# CarloopStick-v1_1.net
KiCad netlist of a schematic drawn in EAGLE
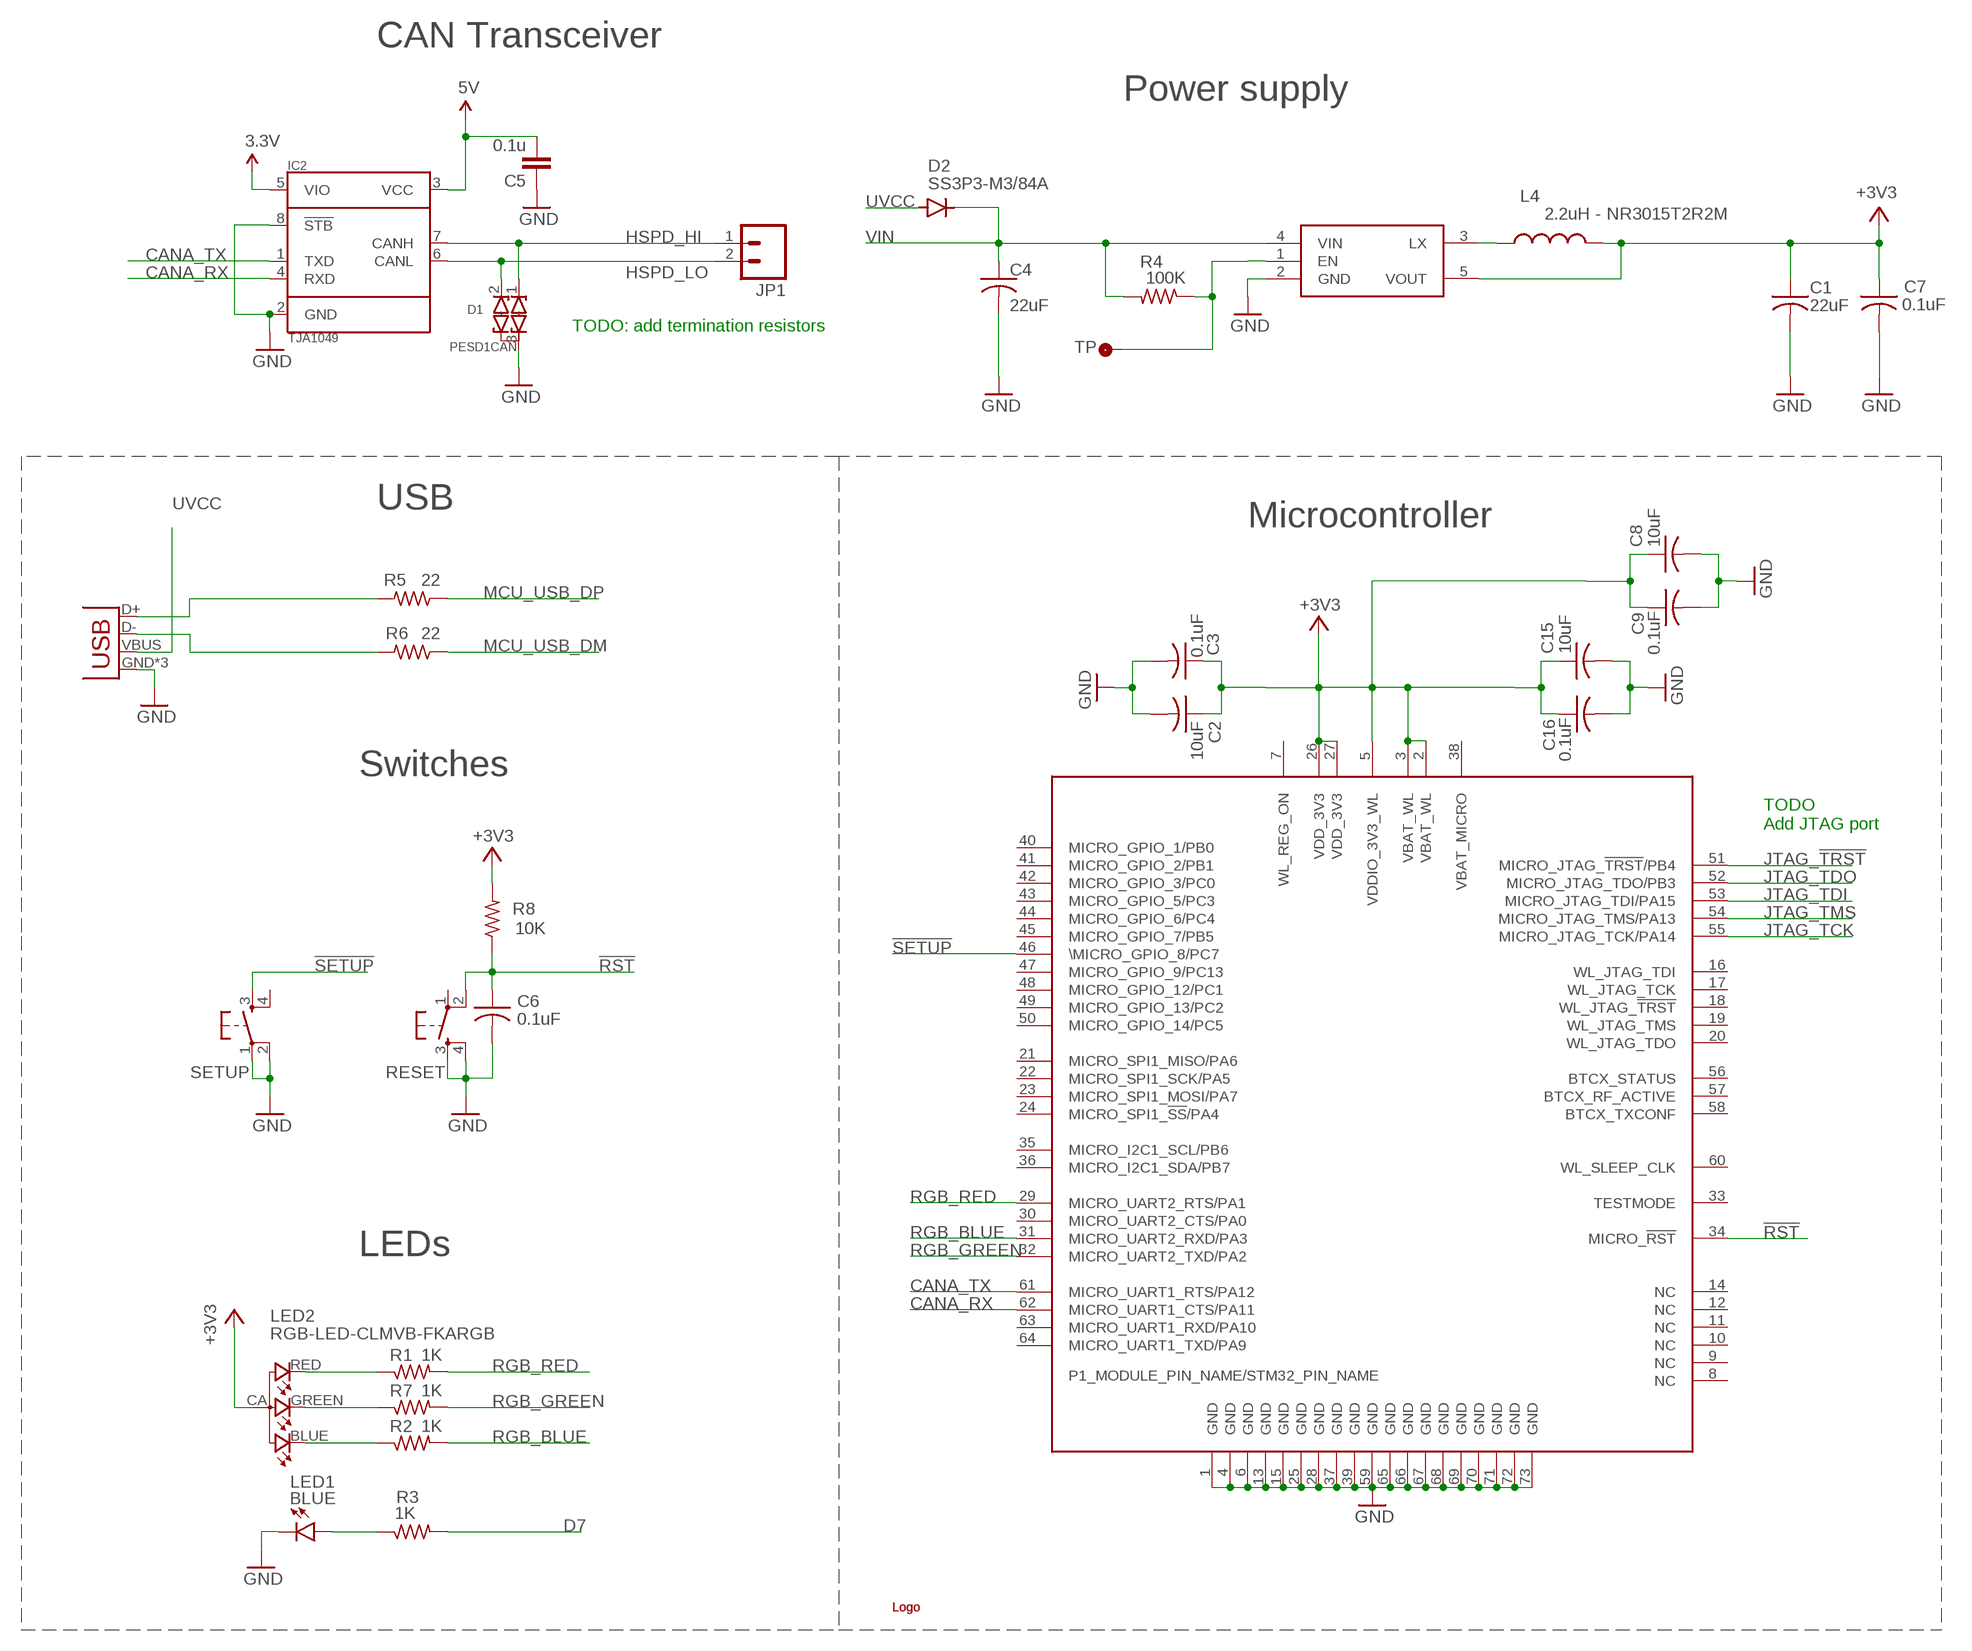
[diagram p0: schematic, sheet 1]

(export (version "E")
  (design (tool "Eeschema 10.0.6"))
  (components
    (comp (ref "C1")
      (value "22uF")
      (footprint "eagle-import:C0603_B")
      (libsource (lib "eagle-import") (part "C-US0603"))
    )
    (comp (ref "C2")
      (value "10uF")
      (footprint "eagle-import:C0603_B")
      (libsource (lib "eagle-import") (part "C-US0603"))
    )
    (comp (ref "C3")
      (value "0.1uF")
      (footprint "eagle-import:C0402_B")
      (libsource (lib "eagle-import") (part "C-US"))
    )
    (comp (ref "C4")
      (value "22uF")
      (footprint "eagle-import:C0603_B")
      (libsource (lib "eagle-import") (part "C-US0603"))
    )
    (comp (ref "C5")
      (value "0.1u")
      (footprint "eagle-import:C0402")
      (fields (field (name "PARTNO") "GRM155R71C104KA88D"))
      (libsource (lib "eagle-import") (part "C-EUC0402"))
    )
    (comp (ref "C6")
      (value "0.1uF")
      (footprint "eagle-import:C0402_B")
      (libsource (lib "eagle-import") (part "C-US"))
    )
    (comp (ref "C7")
      (value "0.1uF")
      (footprint "eagle-import:C0402_B")
      (libsource (lib "eagle-import") (part "C-US"))
    )
    (comp (ref "C8")
      (value "10uF")
      (footprint "eagle-import:C0603_B")
      (libsource (lib "eagle-import") (part "C-US0603"))
    )
    (comp (ref "C9")
      (value "0.1uF")
      (footprint "eagle-import:C0402_B")
      (libsource (lib "eagle-import") (part "C-US"))
    )
    (comp (ref "C15")
      (value "10uF")
      (footprint "eagle-import:C0603_B")
      (libsource (lib "eagle-import") (part "C-US0603"))
    )
    (comp (ref "C16")
      (value "0.1uF")
      (footprint "eagle-import:C0402_B")
      (libsource (lib "eagle-import") (part "C-US"))
    )
    (comp (ref "D1")
      (value "PESD1CAN")
      (footprint "eagle-import:SOT23")
      (fields (field (name "PARTNO") "PESD1CAN-215"))
      (libsource (lib "eagle-import") (part "DIODE_ESD_DUAL-SOT-23"))
    )
    (comp (ref "D2")
      (value "SS3P3-M3/84A")
      (footprint "eagle-import:DIODE-DO-220AA(SMP)")
      (libsource (lib "eagle-import") (part "DIODE"))
    )
    (comp (ref "IC2")
      (value "TJA1049")
      (footprint "eagle-import:SO8")
      (fields (field (name "PARTNO") "TJA1049T-118"))
      (libsource (lib "eagle-import") (part "TJA1049"))
    )
    (comp (ref "JP1")
      (value "M02PTH")
      (footprint "eagle-import:1X02")
      (libsource (lib "eagle-import") (part "M02PTH"))
    )
    (comp (ref "L4")
      (value "2.2uH - NR3015T2R2M")
      (footprint "eagle-import:INDUCTOR-NR3015")
      (libsource (lib "eagle-import") (part "INDUCTORB"))
    )
    (comp (ref "LED2")
      (value "RGB-LED-CLMVB-FKARGB")
      (footprint "eagle-import:PLCC4-2MM-RGB")
      (libsource (lib "eagle-import") (part "RGB-LED-CLMVB-FKARGB"))
    )
    (comp (ref "LED_USR")
      (value "BLUE")
      (footprint "eagle-import:LED-0603-NO-SS")
      (libsource (lib "eagle-import") (part "LED-0603-NO-SS"))
    )
    (comp (ref "R1")
      (value "1K")
      (footprint "eagle-import:R0402_B")
      (libsource (lib "eagle-import") (part "R-US_"))
    )
    (comp (ref "R2")
      (value "1K")
      (footprint "eagle-import:R0402_B")
      (libsource (lib "eagle-import") (part "R-US_"))
    )
    (comp (ref "R3")
      (value "1K")
      (footprint "eagle-import:R0402_B")
      (libsource (lib "eagle-import") (part "R-US_"))
    )
    (comp (ref "R4")
      (value "100K")
      (footprint "eagle-import:R0402_B")
      (libsource (lib "eagle-import") (part "R-US_"))
    )
    (comp (ref "R5")
      (value "22")
      (footprint "eagle-import:R0402_B")
      (libsource (lib "eagle-import") (part "R-US_"))
    )
    (comp (ref "R6")
      (value "22")
      (footprint "eagle-import:R0402_B")
      (libsource (lib "eagle-import") (part "R-US_"))
    )
    (comp (ref "R7")
      (value "1K")
      (footprint "eagle-import:R0402_B")
      (libsource (lib "eagle-import") (part "R-US_"))
    )
    (comp (ref "R8")
      (value "10K")
      (footprint "eagle-import:R0402_B")
      (libsource (lib "eagle-import") (part "R-US_"))
    )
    (comp (ref "RESET")
      (value "KMR211GLFS")
      (footprint "eagle-import:TACTILE_SWITCH_SMD")
      (libsource (lib "eagle-import") (part "TAC_SWITCHSMD"))
    )
    (comp (ref "SETUP")
      (value "KMR211GLFS")
      (footprint "eagle-import:TACTILE_SWITCH_SMD")
      (libsource (lib "eagle-import") (part "TAC_SWITCHSMD"))
    )
    (comp (ref "U$1")
      (value "LOGOSMALL")
      (footprint "eagle-import:CARLOOP-2")
      (libsource (lib "eagle-import") (part "LOGOSMALL"))
    )
    (comp (ref "U$4")
      (value "P1")
      (footprint "eagle-import:WM-N-BM-14")
      (libsource (lib "eagle-import") (part "P1"))
    )
    (comp (ref "U$5")
      (value "LOGOSMALL")
      (footprint "eagle-import:CARLOOP-2")
      (libsource (lib "eagle-import") (part "LOGOSMALL"))
    )
    (comp (ref "U$11")
      (value "R8008-33")
      (footprint "eagle-import:SOT23-5")
      (libsource (lib "eagle-import") (part "R8008-33"))
    )
    (comp (ref "U$12")
      (value "TP3")
      (footprint "eagle-import:TP60_BOT")
      (libsource (lib "eagle-import") (part "TP3"))
    )
    (comp (ref "X1")
      (value "USB-MICROB")
      (footprint "eagle-import:USB-MICROB-SLOT-HOLE")
      (libsource (lib "eagle-import") (part "USBUSB-MICROB-SLOT-HOLE"))
    )
  )
  (nets
    (net (code "1") (name "+3V3") (class "Default")
      (node (ref "C1") (pin "1") (pinfunction "1_1") (pintype "passive"))
      (node (ref "C15") (pin "1") (pinfunction "1_1") (pintype "passive"))
      (node (ref "C16") (pin "1") (pinfunction "1_1") (pintype "passive"))
      (node (ref "C2") (pin "1") (pinfunction "1_1") (pintype "passive"))
      (node (ref "C3") (pin "1") (pinfunction "1_1") (pintype "passive"))
      (node (ref "C7") (pin "1") (pinfunction "1_1") (pintype "passive"))
      (node (ref "C8") (pin "1") (pinfunction "1_1") (pintype "passive"))
      (node (ref "C9") (pin "1") (pinfunction "1_1") (pintype "passive"))
      (node (ref "L4") (pin "2") (pinfunction "2_2") (pintype "passive"))
      (node (ref "LED2") (pin "CA") (pinfunction "1_CA") (pintype "passive"))
      (node (ref "R8") (pin "2") (pinfunction "2_2") (pintype "passive"))
      (node (ref "U$11") (pin "5") (pinfunction "VOUT_5") (pintype "bidirectional"))
      (node (ref "U$4") (pin "2") (pinfunction "VBAT_WL_2") (pintype "bidirectional"))
      (node (ref "U$4") (pin "26") (pinfunction "VDD_3V3_26") (pintype "bidirectional"))
      (node (ref "U$4") (pin "27") (pinfunction "VDD_3V3_27") (pintype "bidirectional"))
      (node (ref "U$4") (pin "3") (pinfunction "VBAT_WL_3") (pintype "bidirectional"))
      (node (ref "U$4") (pin "5") (pinfunction "VDDIO_3V3_WL_5") (pintype "bidirectional"))
    )
    (net (code "2") (name "/CANA_RX") (class "Default")
      (node (ref "IC2") (pin "4") (pinfunction "RXD_4") (pintype "bidirectional"))
      (node (ref "U$4") (pin "62") (pinfunction "MICRO_UART1_CTS/PA11_62") (pintype "bidirectional"))
    )
    (net (code "3") (name "/CANA_TX") (class "Default")
      (node (ref "IC2") (pin "1") (pinfunction "TXD_1") (pintype "bidirectional"))
      (node (ref "U$4") (pin "61") (pinfunction "MICRO_UART1_RTS/PA12_61") (pintype "bidirectional"))
    )
    (net (code "4") (name "/D7") (class "Default")
      (node (ref "R3") (pin "2") (pinfunction "2_2") (pintype "passive"))
    )
    (net (code "5") (name "/HSPD_HI") (class "Default")
      (node (ref "D1") (pin "1") (pinfunction "C1_1") (pintype "power_in"))
      (node (ref "IC2") (pin "7") (pinfunction "CANH_7") (pintype "bidirectional"))
      (node (ref "JP1") (pin "1") (pinfunction "1_1") (pintype "passive"))
    )
    (net (code "6") (name "/HSPD_LO") (class "Default")
      (node (ref "D1") (pin "2") (pinfunction "C2_2") (pintype "power_in"))
      (node (ref "IC2") (pin "6") (pinfunction "CANL_6") (pintype "bidirectional"))
      (node (ref "JP1") (pin "2") (pinfunction "2_2") (pintype "passive"))
    )
    (net (code "7") (name "/JTAG_TCK") (class "Default")
      (node (ref "U$4") (pin "55") (pinfunction "MICRO_JTAG_TCK/PA14_55") (pintype "bidirectional"))
    )
    (net (code "8") (name "/JTAG_TDI") (class "Default")
      (node (ref "U$4") (pin "53") (pinfunction "MICRO_JTAG_TDI/PA15_53") (pintype "bidirectional"))
    )
    (net (code "9") (name "/JTAG_TDO") (class "Default")
      (node (ref "U$4") (pin "52") (pinfunction "MICRO_JTAG_TDO/PB3_52") (pintype "bidirectional"))
    )
    (net (code "10") (name "/JTAG_TMS") (class "Default")
      (node (ref "U$4") (pin "54") (pinfunction "MICRO_JTAG_TMS/PA13_54") (pintype "bidirectional"))
    )
    (net (code "11") (name "/JTAG_~{TRST}") (class "Default")
      (node (ref "U$4") (pin "51") (pinfunction "MICRO_JTAG_~{TRST}/PB4_51") (pintype "bidirectional"))
    )
    (net (code "12") (name "/LED1") (class "Default")
      (node (ref "LED_USR") (pin "A1") (pinfunction "A_A1") (pintype "passive"))
      (node (ref "R3") (pin "1") (pinfunction "1_1") (pintype "passive"))
    )
    (net (code "13") (name "/MCU_USB_DM") (class "Default")
      (node (ref "R6") (pin "1") (pinfunction "1_1") (pintype "passive"))
    )
    (net (code "14") (name "/MCU_USB_DP") (class "Default")
      (node (ref "R5") (pin "1") (pinfunction "1_1") (pintype "passive"))
    )
    (net (code "15") (name "/RGB_BLUE") (class "Default")
      (node (ref "R2") (pin "2") (pinfunction "2_2") (pintype "passive"))
      (node (ref "U$4") (pin "31") (pinfunction "MICRO_UART2_RXD/PA3_31") (pintype "bidirectional"))
    )
    (net (code "16") (name "/RGB_GREEN") (class "Default")
      (node (ref "R7") (pin "2") (pinfunction "2_2") (pintype "passive"))
      (node (ref "U$4") (pin "32") (pinfunction "MICRO_UART2_TXD/PA2_32") (pintype "bidirectional"))
    )
    (net (code "17") (name "/RGB_RED") (class "Default")
      (node (ref "R1") (pin "2") (pinfunction "2_2") (pintype "passive"))
      (node (ref "U$4") (pin "29") (pinfunction "MICRO_UART2_RTS/PA1_29") (pintype "bidirectional"))
    )
    (net (code "18") (name "/UVCC") (class "Default")
      (node (ref "D2") (pin "ANODE") (pinfunction "ANODE_ANODE") (pintype "bidirectional"))
      (node (ref "X1") (pin "VBUS") (pinfunction "VBUS_VBUS") (pintype "bidirectional"))
    )
    (net (code "19") (name "/VIN") (class "Default")
      (node (ref "C4") (pin "1") (pinfunction "1_1") (pintype "passive"))
      (node (ref "D2") (pin "CATHODE") (pinfunction "CATHODE_CATHODE") (pintype "bidirectional"))
      (node (ref "R4") (pin "2") (pinfunction "2_2") (pintype "passive"))
      (node (ref "U$11") (pin "4") (pinfunction "VIN_4") (pintype "bidirectional"))
    )
    (net (code "20") (name "/~{RST}") (class "Default")
      (node (ref "C6") (pin "1") (pinfunction "1_1") (pintype "passive"))
      (node (ref "R8") (pin "1") (pinfunction "1_1") (pintype "passive"))
      (node (ref "RESET") (pin "2") (pinfunction "2_2") (pintype "passive"))
      (node (ref "U$4") (pin "34") (pinfunction "MICRO_~{RST}_34") (pintype "bidirectional"))
    )
    (net (code "21") (name "/~{SETUP}") (class "Default")
      (node (ref "SETUP") (pin "3") (pinfunction "3_3") (pintype "passive"))
      (node (ref "U$4") (pin "46") (pinfunction "\\MICRO_GPIO_8/PC7_46") (pintype "bidirectional"))
    )
    (net (code "22") (name "3.3V") (class "Default")
      (node (ref "IC2") (pin "5") (pinfunction "VIO_5") (pintype "bidirectional"))
    )
    (net (code "23") (name "5V") (class "Default")
      (node (ref "C5") (pin "2") (pinfunction "2_2") (pintype "passive"))
      (node (ref "IC2") (pin "3") (pinfunction "VCC_3") (pintype "bidirectional"))
    )
    (net (code "24") (name "GND") (class "Default")
      (node (ref "C1") (pin "2") (pinfunction "2_2") (pintype "passive"))
      (node (ref "C15") (pin "2") (pinfunction "2_2") (pintype "passive"))
      (node (ref "C16") (pin "2") (pinfunction "2_2") (pintype "passive"))
      (node (ref "C2") (pin "2") (pinfunction "2_2") (pintype "passive"))
      (node (ref "C3") (pin "2") (pinfunction "2_2") (pintype "passive"))
      (node (ref "C4") (pin "2") (pinfunction "2_2") (pintype "passive"))
      (node (ref "C5") (pin "1") (pinfunction "1_1") (pintype "passive"))
      (node (ref "C6") (pin "2") (pinfunction "2_2") (pintype "passive"))
      (node (ref "C7") (pin "2") (pinfunction "2_2") (pintype "passive"))
      (node (ref "C8") (pin "2") (pinfunction "2_2") (pintype "passive"))
      (node (ref "C9") (pin "2") (pinfunction "2_2") (pintype "passive"))
      (node (ref "D1") (pin "3") (pinfunction "COM_3") (pintype "power_in"))
      (node (ref "IC2") (pin "2") (pinfunction "GND_2") (pintype "bidirectional"))
      (node (ref "IC2") (pin "8") (pinfunction "~{STB}_8") (pintype "bidirectional"))
      (node (ref "LED_USR") (pin "C1") (pinfunction "C_C1") (pintype "passive"))
      (node (ref "RESET") (pin "3") (pinfunction "3_3") (pintype "passive"))
      (node (ref "RESET") (pin "4") (pinfunction "4_4") (pintype "passive"))
      (node (ref "SETUP") (pin "1") (pinfunction "1_1") (pintype "passive"))
      (node (ref "SETUP") (pin "2") (pinfunction "2_2") (pintype "passive"))
      (node (ref "U$11") (pin "2") (pinfunction "GND_2") (pintype "bidirectional"))
      (node (ref "U$4") (pin "1") (pinfunction "GND_1") (pintype "bidirectional"))
      (node (ref "U$4") (pin "13") (pinfunction "GND_13") (pintype "bidirectional"))
      (node (ref "U$4") (pin "15") (pinfunction "GND_15") (pintype "bidirectional"))
      (node (ref "U$4") (pin "25") (pinfunction "GND_25") (pintype "bidirectional"))
      (node (ref "U$4") (pin "28") (pinfunction "GND_28") (pintype "bidirectional"))
      (node (ref "U$4") (pin "37") (pinfunction "GND_37") (pintype "bidirectional"))
      (node (ref "U$4") (pin "39") (pinfunction "GND_39") (pintype "bidirectional"))
      (node (ref "U$4") (pin "4") (pinfunction "GND_4") (pintype "bidirectional"))
      (node (ref "U$4") (pin "59") (pinfunction "GND_59") (pintype "bidirectional"))
      (node (ref "U$4") (pin "6") (pinfunction "GND_6") (pintype "bidirectional"))
      (node (ref "U$4") (pin "65") (pinfunction "GND_65") (pintype "bidirectional"))
      (node (ref "U$4") (pin "66") (pinfunction "GND_66") (pintype "bidirectional"))
      (node (ref "U$4") (pin "67") (pinfunction "GND_67") (pintype "bidirectional"))
      (node (ref "U$4") (pin "68") (pinfunction "GND_68") (pintype "bidirectional"))
      (node (ref "U$4") (pin "69") (pinfunction "GND_69") (pintype "bidirectional"))
      (node (ref "U$4") (pin "70") (pinfunction "GND_70") (pintype "bidirectional"))
      (node (ref "U$4") (pin "71") (pinfunction "GND_71") (pintype "bidirectional"))
      (node (ref "U$4") (pin "72") (pinfunction "GND_72") (pintype "bidirectional"))
      (node (ref "U$4") (pin "73") (pinfunction "GND_73") (pintype "bidirectional"))
      (node (ref "X1") (pin "GND") (pinfunction "GND_GND") (pintype "bidirectional"))
      (node (ref "X1") (pin "MT1") (pinfunction "GND_MT1") (pintype "bidirectional"))
      (node (ref "X1") (pin "MT2") (pinfunction "GND_MT2") (pintype "bidirectional"))
    )
    (net (code "25") (name "Net-(LED2-2)") (class "Default")
      (node (ref "LED2") (pin "BLUE") (pinfunction "2_BLUE") (pintype "passive"))
      (node (ref "R2") (pin "1") (pinfunction "1_1") (pintype "passive"))
    )
    (net (code "26") (name "Net-(LED2-3)") (class "Default")
      (node (ref "LED2") (pin "GREEN") (pinfunction "3_GREEN") (pintype "passive"))
      (node (ref "R7") (pin "1") (pinfunction "1_1") (pintype "passive"))
    )
    (net (code "27") (name "Net-(LED2-4)") (class "Default")
      (node (ref "LED2") (pin "RED") (pinfunction "4_RED") (pintype "passive"))
      (node (ref "R1") (pin "1") (pinfunction "1_1") (pintype "passive"))
    )
    (net (code "28") (name "Net-(R5-Pad2)") (class "Default")
      (node (ref "R5") (pin "2") (pinfunction "2_2") (pintype "passive"))
      (node (ref "X1") (pin "D+") (pinfunction "D+_D+") (pintype "bidirectional"))
    )
    (net (code "29") (name "Net-(R6-Pad2)") (class "Default")
      (node (ref "R6") (pin "2") (pinfunction "2_2") (pintype "passive"))
      (node (ref "X1") (pin "D-") (pinfunction "D-_D-") (pintype "bidirectional"))
    )
    (net (code "30") (name "Net-(U$11-EN)") (class "Default")
      (node (ref "R4") (pin "1") (pinfunction "1_1") (pintype "passive"))
      (node (ref "U$11") (pin "1") (pinfunction "EN_1") (pintype "bidirectional"))
      (node (ref "U$12") (pin "P$1") (pinfunction "TP_P$1") (pintype "bidirectional"))
    )
    (net (code "31") (name "Net-(U$11-LX)") (class "Default")
      (node (ref "L4") (pin "1") (pinfunction "1_1") (pintype "passive"))
      (node (ref "U$11") (pin "3") (pinfunction "LX_3") (pintype "bidirectional"))
    )
    (net (code "32") (name "unconnected-(RESET-Pad1)") (class "Default")
      (node (ref "RESET") (pin "1") (pinfunction "1_1") (pintype "passive"))
    )
    (net (code "33") (name "unconnected-(SETUP-Pad4)") (class "Default")
      (node (ref "SETUP") (pin "4") (pinfunction "4_4") (pintype "passive"))
    )
    (net (code "34") (name "unconnected-(U$4-BTCX_RF_ACTIVE-Pad57)") (class "Default")
      (node (ref "U$4") (pin "57") (pinfunction "BTCX_RF_ACTIVE_57") (pintype "bidirectional"))
    )
    (net (code "35") (name "unconnected-(U$4-BTCX_STATUS-Pad56)") (class "Default")
      (node (ref "U$4") (pin "56") (pinfunction "BTCX_STATUS_56") (pintype "bidirectional"))
    )
    (net (code "36") (name "unconnected-(U$4-BTCX_TXCONF-Pad58)") (class "Default")
      (node (ref "U$4") (pin "58") (pinfunction "BTCX_TXCONF_58") (pintype "bidirectional"))
    )
    (net (code "37") (name "unconnected-(U$4-MICRO_GPIO_1{slash}PB0-Pad40)") (class "Default")
      (node (ref "U$4") (pin "40") (pinfunction "MICRO_GPIO_1/PB0_40") (pintype "bidirectional"))
    )
    (net (code "38") (name "unconnected-(U$4-MICRO_GPIO_2{slash}PB1-Pad41)") (class "Default")
      (node (ref "U$4") (pin "41") (pinfunction "MICRO_GPIO_2/PB1_41") (pintype "bidirectional"))
    )
    (net (code "39") (name "unconnected-(U$4-MICRO_GPIO_3{slash}PC0-Pad42)") (class "Default")
      (node (ref "U$4") (pin "42") (pinfunction "MICRO_GPIO_3/PC0_42") (pintype "bidirectional"))
    )
    (net (code "40") (name "unconnected-(U$4-MICRO_GPIO_5{slash}PC3-Pad43)") (class "Default")
      (node (ref "U$4") (pin "43") (pinfunction "MICRO_GPIO_5/PC3_43") (pintype "bidirectional"))
    )
    (net (code "41") (name "unconnected-(U$4-MICRO_GPIO_6{slash}PC4-Pad44)") (class "Default")
      (node (ref "U$4") (pin "44") (pinfunction "MICRO_GPIO_6/PC4_44") (pintype "bidirectional"))
    )
    (net (code "42") (name "unconnected-(U$4-MICRO_GPIO_7{slash}PB5-Pad45)") (class "Default")
      (node (ref "U$4") (pin "45") (pinfunction "MICRO_GPIO_7/PB5_45") (pintype "bidirectional"))
    )
    (net (code "43") (name "unconnected-(U$4-MICRO_GPIO_9{slash}PC13-Pad47)") (class "Default")
      (node (ref "U$4") (pin "47") (pinfunction "MICRO_GPIO_9/PC13_47") (pintype "bidirectional"))
    )
    (net (code "44") (name "unconnected-(U$4-MICRO_GPIO_12{slash}PC1-Pad48)") (class "Default")
      (node (ref "U$4") (pin "48") (pinfunction "MICRO_GPIO_12/PC1_48") (pintype "bidirectional"))
    )
    (net (code "45") (name "unconnected-(U$4-MICRO_GPIO_13{slash}PC2-Pad49)") (class "Default")
      (node (ref "U$4") (pin "49") (pinfunction "MICRO_GPIO_13/PC2_49") (pintype "bidirectional"))
    )
    (net (code "46") (name "unconnected-(U$4-MICRO_GPIO_14{slash}PC5-Pad50)") (class "Default")
      (node (ref "U$4") (pin "50") (pinfunction "MICRO_GPIO_14/PC5_50") (pintype "bidirectional"))
    )
    (net (code "47") (name "unconnected-(U$4-MICRO_I2C1_SCL{slash}PB6-Pad35)") (class "Default")
      (node (ref "U$4") (pin "35") (pinfunction "MICRO_I2C1_SCL/PB6_35") (pintype "bidirectional"))
    )
    (net (code "48") (name "unconnected-(U$4-MICRO_I2C1_SDA{slash}PB7-Pad36)") (class "Default")
      (node (ref "U$4") (pin "36") (pinfunction "MICRO_I2C1_SDA/PB7_36") (pintype "bidirectional"))
    )
    (net (code "49") (name "unconnected-(U$4-MICRO_SPI1_MISO{slash}PA6-Pad21)") (class "Default")
      (node (ref "U$4") (pin "21") (pinfunction "MICRO_SPI1_MISO/PA6_21") (pintype "bidirectional"))
    )
    (net (code "50") (name "unconnected-(U$4-MICRO_SPI1_MOSI{slash}PA7-Pad23)") (class "Default")
      (node (ref "U$4") (pin "23") (pinfunction "MICRO_SPI1_MOSI/PA7_23") (pintype "bidirectional"))
    )
    (net (code "51") (name "unconnected-(U$4-MICRO_SPI1_SCK{slash}PA5-Pad22)") (class "Default")
      (node (ref "U$4") (pin "22") (pinfunction "MICRO_SPI1_SCK/PA5_22") (pintype "bidirectional"))
    )
    (net (code "52") (name "unconnected-(U$4-MICRO_SPI1_~{SS}{slash}PA4-Pad24)") (class "Default")
      (node (ref "U$4") (pin "24") (pinfunction "MICRO_SPI1_~{SS}/PA4_24") (pintype "bidirectional"))
    )
    (net (code "53") (name "unconnected-(U$4-MICRO_UART1_RXD{slash}PA10-Pad63)") (class "Default")
      (node (ref "U$4") (pin "63") (pinfunction "MICRO_UART1_RXD/PA10_63") (pintype "bidirectional"))
    )
    (net (code "54") (name "unconnected-(U$4-MICRO_UART1_TXD{slash}PA9-Pad64)") (class "Default")
      (node (ref "U$4") (pin "64") (pinfunction "MICRO_UART1_TXD/PA9_64") (pintype "bidirectional"))
    )
    (net (code "55") (name "unconnected-(U$4-MICRO_UART2_CTS{slash}PA0-Pad30)") (class "Default")
      (node (ref "U$4") (pin "30") (pinfunction "MICRO_UART2_CTS/PA0_30") (pintype "bidirectional"))
    )
    (net (code "56") (name "unconnected-(U$4-NC-Pad8)") (class "Default")
      (node (ref "U$4") (pin "8") (pinfunction "NC_8") (pintype "bidirectional"))
    )
    (net (code "57") (name "unconnected-(U$4-NC-Pad9)") (class "Default")
      (node (ref "U$4") (pin "9") (pinfunction "NC_9") (pintype "bidirectional"))
    )
    (net (code "58") (name "unconnected-(U$4-NC-Pad10)") (class "Default")
      (node (ref "U$4") (pin "10") (pinfunction "NC_10") (pintype "bidirectional"))
    )
    (net (code "59") (name "unconnected-(U$4-NC-Pad11)") (class "Default")
      (node (ref "U$4") (pin "11") (pinfunction "NC_11") (pintype "bidirectional"))
    )
    (net (code "60") (name "unconnected-(U$4-NC-Pad12)") (class "Default")
      (node (ref "U$4") (pin "12") (pinfunction "NC_12") (pintype "bidirectional"))
    )
    (net (code "61") (name "unconnected-(U$4-NC-Pad14)") (class "Default")
      (node (ref "U$4") (pin "14") (pinfunction "NC_14") (pintype "bidirectional"))
    )
    (net (code "62") (name "unconnected-(U$4-TESTMODE-Pad33)") (class "Default")
      (node (ref "U$4") (pin "33") (pinfunction "TESTMODE_33") (pintype "bidirectional"))
    )
    (net (code "63") (name "unconnected-(U$4-VBAT_MICRO-Pad38)") (class "Default")
      (node (ref "U$4") (pin "38") (pinfunction "VBAT_MICRO_38") (pintype "bidirectional"))
    )
    (net (code "64") (name "unconnected-(U$4-WL_JTAG_TCK-Pad17)") (class "Default")
      (node (ref "U$4") (pin "17") (pinfunction "WL_JTAG_TCK_17") (pintype "bidirectional"))
    )
    (net (code "65") (name "unconnected-(U$4-WL_JTAG_TDI-Pad16)") (class "Default")
      (node (ref "U$4") (pin "16") (pinfunction "WL_JTAG_TDI_16") (pintype "bidirectional"))
    )
    (net (code "66") (name "unconnected-(U$4-WL_JTAG_TDO-Pad20)") (class "Default")
      (node (ref "U$4") (pin "20") (pinfunction "WL_JTAG_TDO_20") (pintype "bidirectional"))
    )
    (net (code "67") (name "unconnected-(U$4-WL_JTAG_TMS-Pad19)") (class "Default")
      (node (ref "U$4") (pin "19") (pinfunction "WL_JTAG_TMS_19") (pintype "bidirectional"))
    )
    (net (code "68") (name "unconnected-(U$4-WL_JTAG_~{TRST}-Pad18)") (class "Default")
      (node (ref "U$4") (pin "18") (pinfunction "WL_JTAG_~{TRST}_18") (pintype "bidirectional"))
    )
    (net (code "69") (name "unconnected-(U$4-WL_REG_ON-Pad7)") (class "Default")
      (node (ref "U$4") (pin "7") (pinfunction "WL_REG_ON_7") (pintype "bidirectional"))
    )
    (net (code "70") (name "unconnected-(U$4-WL_SLEEP_CLK-Pad60)") (class "Default")
      (node (ref "U$4") (pin "60") (pinfunction "WL_SLEEP_CLK_60") (pintype "bidirectional"))
    )
  )
)
